# logger_mcu.net
KiCad netlist of a schematic drawn in Altium Designer
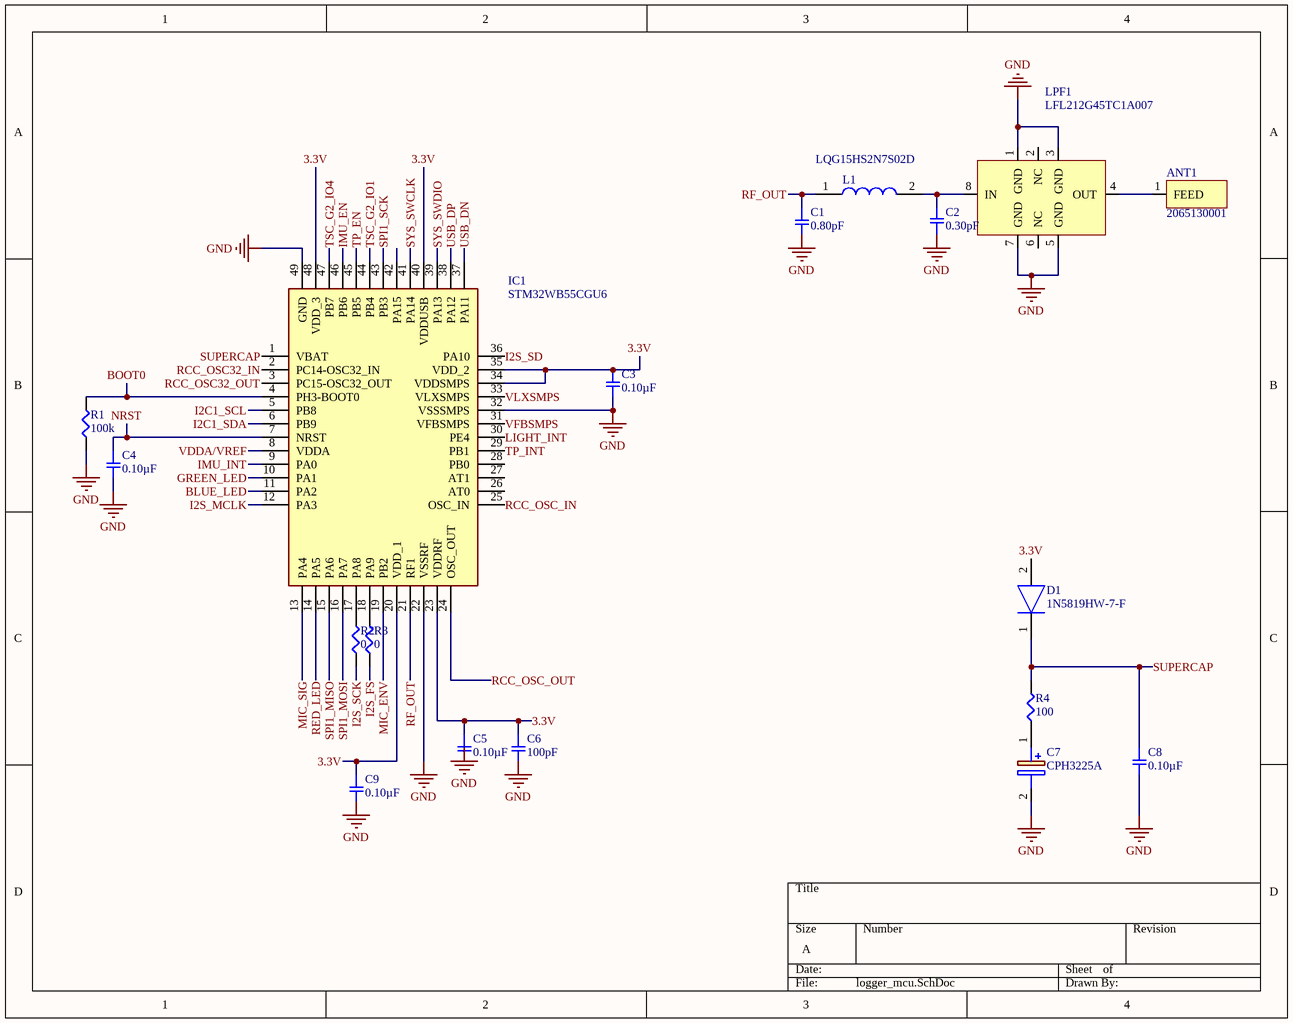
[diagram p0: logger_mcu.SchDoc]

(export (version "E")
  (design (tool "Eeschema 10.0.6"))
  (components
    (comp (ref "ANT1")
      (value "2065130001")
      (footprint "2065130001")
      (libsource (lib "schematic_components") (part "2065130001"))
    )
    (comp (ref "C1")
      (value "0.80pF")
      (footprint "SMD-0402C")
      (description "CAP CER 0.8PF 50V NP0 0402")
      (fields
        (field (name "DIGI-KEY PART NUMBER") "490-6269-1-ND")
        (field (name "PART NUMBER") "GRM1555C1HR80BA01D")
      )
      (libsource (lib "capacitor_murata_0402") (part "GRM1555C1HR80BA01D"))
    )
    (comp (ref "C2")
      (value "0.30pF")
      (footprint "SMD-0402C")
      (description "CAP CER 0.3PF 50V NP0 0402")
      (fields
        (field (name "DIGI-KEY PART NUMBER") "490-6261-1-ND")
        (field (name "PART NUMBER") "GRM1555C1HR30WA01D")
      )
      (libsource (lib "capacitor_murata_0402") (part "GRM1555C1HR30WA01D"))
    )
    (comp (ref "C3")
      (value "0.10µF")
      (footprint "SMD-0402C")
      (description "CAP CER 0.1UF 16V X7R 0402")
      (fields
        (field (name "DIGI-KEY PART NUMBER") "490-4759-1-ND")
        (field (name "PART NUMBER") "GCM155R71C104KA55D")
      )
      (libsource (lib "capacitor_murata_0402") (part "GCM155R71C104KA55D"))
    )
    (comp (ref "C4")
      (value "0.10µF")
      (footprint "SMD-0402C")
      (description "CAP CER 0.1UF 16V X7R 0402")
      (fields
        (field (name "DIGI-KEY PART NUMBER") "490-4759-1-ND")
        (field (name "PART NUMBER") "GCM155R71C104KA55D")
      )
      (libsource (lib "capacitor_murata_0402") (part "GCM155R71C104KA55D"))
    )
    (comp (ref "C5")
      (value "0.10µF")
      (footprint "SMD-0402C")
      (description "CAP CER 0.1UF 16V X7R 0402")
      (fields
        (field (name "DIGI-KEY PART NUMBER") "490-4759-1-ND")
        (field (name "PART NUMBER") "GCM155R71C104KA55D")
      )
      (libsource (lib "capacitor_murata_0402") (part "GCM155R71C104KA55D"))
    )
    (comp (ref "C6")
      (value "100pF")
      (footprint "SMD-0402C")
      (description "CAP CER 100PF 50V NP0 0402")
      (fields
        (field (name "DIGI-KEY PART NUMBER") "490-10669-1-ND")
        (field (name "PART NUMBER") "GCM1555C1H101JA16D")
      )
      (libsource (lib "capacitor_murata_0402") (part "GCM1555C1H101JA16D"))
    )
    (comp (ref "C7")
      (value "CPH3225A")
      (footprint "SamacSys:CPH3225A")
      (description "Capacitor Polarised")
      (fields (field (name "MOUSER PART NUMBER") "628-CPH3225A"))
      (libsource (lib "*") (part "CPH3225A"))
    )
    (comp (ref "C8")
      (value "0.10µF")
      (footprint "SMD-0402C")
      (description "CAP CER 0.1UF 16V X7R 0402")
      (fields
        (field (name "DIGI-KEY PART NUMBER") "490-4759-1-ND")
        (field (name "PART NUMBER") "GCM155R71C104KA55D")
      )
      (libsource (lib "capacitor_murata_0402") (part "GCM155R71C104KA55D"))
    )
    (comp (ref "C9")
      (value "0.10µF")
      (footprint "SMD-0402C")
      (description "CAP CER 0.1UF 16V X7R 0402")
      (fields
        (field (name "DIGI-KEY PART NUMBER") "490-4759-1-ND")
        (field (name "PART NUMBER") "GCM155R71C104KA55D")
      )
      (libsource (lib "capacitor_murata_0402") (part "GCM155R71C104KA55D"))
    )
    (comp (ref "D1")
      (value "1N5819HW-7-F")
      (footprint "SamacSys:SOD3716X145N")
      (description "Diode")
      (fields (field (name "MOUSER PART NUMBER") "621-1N5819HW-F") (field (name "RS PART NUMBER") "7082197P"))
      (libsource (lib "*") (part "1N5819HW-7-F"))
    )
    (comp (ref "IC1")
      (value "STM32WB55CGU6")
      (footprint "SamacSys:QFN50P700X700X65-49N-D")
      (description "Integrated Circuit")
      (fields (field (name "MOUSER PART NUMBER") "511-STM32WB55CGU6"))
      (libsource (lib "SamacSys") (part "STM32WB55CGU6"))
    )
    (comp (ref "L1")
      (value "LQG15HS2N7S02D")
      (footprint "SamacSys:INDC1005X55N")
      (description "Inductor")
      (libsource (lib "SamacSys") (part "LQG15HS2N7S02D"))
    )
    (comp (ref "LPF1")
      (value "LFL212G45TC1A007")
      (footprint "LFL212G45TC1A007")
      (libsource (lib "SamacSys") (part "LFL212G45TC1A007"))
    )
    (comp (ref "R1")
      (value "100k")
      (footprint "SMD-0402-RES")
      (description "RES SMD 100K OHM 1% 1/10W 0402")
      (fields
        (field (name "PART NUMBER") "ERJ-2RKF1003X")
        (field (name "DIGI-KEY PART NUMBER") "P100KLCT-ND")
      )
      (libsource (lib "Panasonic_ERJ_0402") (part "ERJ-2RKF1003X"))
    )
    (comp (ref "R2")
      (value "0")
      (footprint "SMD-0402-RES")
      (description "RES SMD 0K OHM 5% 1/10W 0402")
      (fields (field (name "PART NUMBER") "ERJ-2GEJ103X") (field (name "DIGI-KEY PART NUMBER") "P10KJCT-ND"))
      (libsource (lib "Panasonic_ERJ_0402") (part "ERJ-2GEJ103X"))
    )
    (comp (ref "R3")
      (value "0")
      (footprint "SMD-0402-RES")
      (description "RES SMD 0K OHM 5% 1/10W 0402")
      (fields (field (name "PART NUMBER") "ERJ-2GEJ103X") (field (name "DIGI-KEY PART NUMBER") "P10KJCT-ND"))
      (libsource (lib "Panasonic_ERJ_0402") (part "ERJ-2GEJ103X"))
    )
    (comp (ref "R4")
      (value "100")
      (footprint "SMD-0402-RES")
      (description "RES SMD 100 OHM 5% 1/4W 0603")
      (fields
        (field (name "PART NUMBER") "ERJ-2RKF1003X")
        (field (name "DIGI-KEY PART NUMBER") "P100KLCT-ND")
      )
      (libsource (lib "Panasonic_ERJ_0402") (part "ERJ-2RKF1003X"))
    )
  )
  (nets
    (net (code "1") (name "/3.3V") (class "Default")
      (node (ref "C3") (pin "1") (pinfunction "1_1") (pintype "passive"))
      (node (ref "C5") (pin "1") (pinfunction "1_1") (pintype "passive"))
      (node (ref "C6") (pin "1") (pinfunction "1_1") (pintype "passive"))
      (node (ref "C9") (pin "1") (pinfunction "1_1") (pintype "passive"))
      (node (ref "D1") (pin "2") (pinfunction "A_2") (pintype "passive"))
      (node (ref "IC1") (pin "20") (pinfunction "VDD_1_20") (pintype "passive"))
      (node (ref "IC1") (pin "23") (pinfunction "VDDRF_23") (pintype "passive"))
      (node (ref "IC1") (pin "34") (pinfunction "VDDSMPS_34") (pintype "passive"))
      (node (ref "IC1") (pin "35") (pinfunction "VDD_2_35") (pintype "passive"))
      (node (ref "IC1") (pin "40") (pinfunction "VDDUSB_40") (pintype "passive"))
      (node (ref "IC1") (pin "48") (pinfunction "VDD_3_48") (pintype "passive"))
    )
    (net (code "2") (name "/BLUE_LED") (class "Default")
      (node (ref "IC1") (pin "11") (pinfunction "PA2_11") (pintype "passive"))
    )
    (net (code "3") (name "/BOOT0") (class "Default")
      (node (ref "IC1") (pin "4") (pinfunction "PH3-BOOT0_4") (pintype "passive"))
      (node (ref "R1") (pin "2") (pinfunction "2_2") (pintype "passive"))
    )
    (net (code "4") (name "/GREEN_LED") (class "Default")
      (node (ref "IC1") (pin "10") (pinfunction "PA1_10") (pintype "passive"))
    )
    (net (code "5") (name "/I2C1_SCL") (class "Default")
      (node (ref "IC1") (pin "5") (pinfunction "PB8_5") (pintype "passive"))
    )
    (net (code "6") (name "/I2C1_SDA") (class "Default")
      (node (ref "IC1") (pin "6") (pinfunction "PB9_6") (pintype "passive"))
    )
    (net (code "7") (name "/I2S_FS") (class "Default")
      (node (ref "R3") (pin "1") (pinfunction "1_1") (pintype "passive"))
    )
    (net (code "8") (name "/I2S_MCLK") (class "Default")
      (node (ref "IC1") (pin "12") (pinfunction "PA3_12") (pintype "passive"))
    )
    (net (code "9") (name "/I2S_SCK") (class "Default")
      (node (ref "R2") (pin "1") (pinfunction "1_1") (pintype "passive"))
    )
    (net (code "10") (name "/I2S_SD") (class "Default")
      (node (ref "IC1") (pin "36") (pinfunction "PA10_36") (pintype "passive"))
    )
    (net (code "11") (name "/IMU_EN") (class "Default")
      (node (ref "IC1") (pin "46") (pinfunction "PB6_46") (pintype "passive"))
    )
    (net (code "12") (name "/IMU_INT") (class "Default")
      (node (ref "IC1") (pin "9") (pinfunction "PA0_9") (pintype "passive"))
    )
    (net (code "13") (name "/LIGHT_INT") (class "Default")
      (node (ref "IC1") (pin "30") (pinfunction "PE4_30") (pintype "passive"))
    )
    (net (code "14") (name "/MIC_ENV") (class "Default")
      (node (ref "IC1") (pin "19") (pinfunction "PB2_19") (pintype "passive"))
    )
    (net (code "15") (name "/MIC_SIG") (class "Default")
      (node (ref "IC1") (pin "13") (pinfunction "PA4_13") (pintype "passive"))
    )
    (net (code "16") (name "/NRST") (class "Default")
      (node (ref "C4") (pin "1") (pinfunction "1_1") (pintype "passive"))
      (node (ref "IC1") (pin "7") (pinfunction "NRST_7") (pintype "passive"))
    )
    (net (code "17") (name "/RCC_OSC32_IN") (class "Default")
      (node (ref "IC1") (pin "2") (pinfunction "PC14-OSC32_IN_2") (pintype "passive"))
    )
    (net (code "18") (name "/RCC_OSC32_OUT") (class "Default")
      (node (ref "IC1") (pin "3") (pinfunction "PC15-OSC32_OUT_3") (pintype "passive"))
    )
    (net (code "19") (name "/RCC_OSC_IN") (class "Default")
      (node (ref "IC1") (pin "25") (pinfunction "OSC_IN_25") (pintype "passive"))
    )
    (net (code "20") (name "/RCC_OSC_OUT") (class "Default")
      (node (ref "IC1") (pin "24") (pinfunction "OSC_OUT_24") (pintype "passive"))
    )
    (net (code "21") (name "/RED_LED") (class "Default")
      (node (ref "IC1") (pin "14") (pinfunction "PA5_14") (pintype "passive"))
    )
    (net (code "22") (name "/RF_OUT") (class "Default")
      (node (ref "C1") (pin "1") (pinfunction "1_1") (pintype "passive"))
      (node (ref "IC1") (pin "21") (pinfunction "RF1_21") (pintype "passive"))
      (node (ref "L1") (pin "1") (pinfunction "1_1") (pintype "passive"))
    )
    (net (code "23") (name "/SPI1_MISO") (class "Default")
      (node (ref "IC1") (pin "15") (pinfunction "PA6_15") (pintype "passive"))
    )
    (net (code "24") (name "/SPI1_MOSI") (class "Default")
      (node (ref "IC1") (pin "16") (pinfunction "PA7_16") (pintype "passive"))
    )
    (net (code "25") (name "/SPI1_SCK") (class "Default")
      (node (ref "IC1") (pin "43") (pinfunction "PB3_43") (pintype "passive"))
    )
    (net (code "26") (name "/SUPERCAP") (class "Default")
      (node (ref "C8") (pin "1") (pinfunction "1_1") (pintype "passive"))
      (node (ref "D1") (pin "1") (pinfunction "K_1") (pintype "passive"))
      (node (ref "IC1") (pin "1") (pinfunction "VBAT_1") (pintype "passive"))
      (node (ref "R4") (pin "2") (pinfunction "2_2") (pintype "passive"))
    )
    (net (code "27") (name "/SYS_SWCLK") (class "Default")
      (node (ref "IC1") (pin "41") (pinfunction "PA14_41") (pintype "passive"))
    )
    (net (code "28") (name "/SYS_SWDIO") (class "Default")
      (node (ref "IC1") (pin "39") (pinfunction "PA13_39") (pintype "passive"))
    )
    (net (code "29") (name "/TP_EN") (class "Default")
      (node (ref "IC1") (pin "45") (pinfunction "PB5_45") (pintype "passive"))
    )
    (net (code "30") (name "/TP_INT") (class "Default")
      (node (ref "IC1") (pin "29") (pinfunction "PB1_29") (pintype "passive"))
    )
    (net (code "31") (name "/TSC_G2_IO1") (class "Default")
      (node (ref "IC1") (pin "44") (pinfunction "PB4_44") (pintype "passive"))
    )
    (net (code "32") (name "/TSC_G2_IO4") (class "Default")
      (node (ref "IC1") (pin "47") (pinfunction "PB7_47") (pintype "passive"))
    )
    (net (code "33") (name "/USB_DN") (class "Default")
      (node (ref "IC1") (pin "37") (pinfunction "PA11_37") (pintype "passive"))
    )
    (net (code "34") (name "/USB_DP") (class "Default")
      (node (ref "IC1") (pin "38") (pinfunction "PA12_38") (pintype "passive"))
    )
    (net (code "35") (name "/VDDA{slash}VREF") (class "Default")
      (node (ref "IC1") (pin "8") (pinfunction "VDDA_8") (pintype "passive"))
    )
    (net (code "36") (name "/VFBSMPS") (class "Default")
      (node (ref "IC1") (pin "31") (pinfunction "VFBSMPS_31") (pintype "passive"))
    )
    (net (code "37") (name "/VLXSMPS") (class "Default")
      (node (ref "IC1") (pin "33") (pinfunction "VLXSMPS_33") (pintype "passive"))
    )
    (net (code "38") (name "GND") (class "Default")
      (node (ref "C1") (pin "2") (pinfunction "2_2") (pintype "passive"))
      (node (ref "C2") (pin "1") (pinfunction "1_1") (pintype "passive"))
      (node (ref "C3") (pin "2") (pinfunction "2_2") (pintype "passive"))
      (node (ref "C4") (pin "2") (pinfunction "2_2") (pintype "passive"))
      (node (ref "C6") (pin "2") (pinfunction "2_2") (pintype "passive"))
      (node (ref "C7") (pin "2") (pinfunction "-_2") (pintype "passive"))
      (node (ref "C8") (pin "2") (pinfunction "2_2") (pintype "passive"))
      (node (ref "C9") (pin "2") (pinfunction "2_2") (pintype "passive"))
      (node (ref "IC1") (pin "22") (pinfunction "VSSRF_22") (pintype "passive"))
      (node (ref "IC1") (pin "32") (pinfunction "VSSSMPS_32") (pintype "passive"))
      (node (ref "IC1") (pin "49") (pinfunction "GND_49") (pintype "passive"))
      (node (ref "LPF1") (pin "1") (pinfunction "GND_1") (pintype "passive"))
      (node (ref "LPF1") (pin "3") (pinfunction "GND_3") (pintype "passive"))
      (node (ref "LPF1") (pin "5") (pinfunction "GND_5") (pintype "passive"))
      (node (ref "LPF1") (pin "7") (pinfunction "GND_7") (pintype "passive"))
      (node (ref "R1") (pin "1") (pinfunction "1_1") (pintype "passive"))
    )
    (net (code "39") (name "Net-(ANT1-FEED)") (class "Default")
      (node (ref "ANT1") (pin "1") (pinfunction "FEED_1") (pintype "passive"))
      (node (ref "LPF1") (pin "4") (pinfunction "OUT_4") (pintype "passive"))
    )
    (net (code "40") (name "Net-(C7-+)") (class "Default")
      (node (ref "C7") (pin "1") (pinfunction "+_1") (pintype "passive"))
      (node (ref "R4") (pin "1") (pinfunction "1_1") (pintype "passive"))
    )
    (net (code "41") (name "Net-(IC1-PA8)") (class "Default")
      (node (ref "IC1") (pin "17") (pinfunction "PA8_17") (pintype "passive"))
      (node (ref "R2") (pin "2") (pinfunction "2_2") (pintype "passive"))
    )
    (net (code "42") (name "Net-(IC1-PA9)") (class "Default")
      (node (ref "IC1") (pin "18") (pinfunction "PA9_18") (pintype "passive"))
      (node (ref "R3") (pin "2") (pinfunction "2_2") (pintype "passive"))
    )
    (net (code "43") (name "Net-(LPF1-IN)") (class "Default")
      (node (ref "C2") (pin "2") (pinfunction "2_2") (pintype "passive"))
      (node (ref "L1") (pin "2") (pinfunction "2_2") (pintype "passive"))
      (node (ref "LPF1") (pin "8") (pinfunction "IN_8") (pintype "passive"))
    )
    (net (code "44") (name "unconnected-(C5-Pad2)") (class "Default")
      (node (ref "C5") (pin "2") (pinfunction "2_2") (pintype "passive"))
    )
    (net (code "45") (name "unconnected-(IC1-AT0-Pad26)") (class "Default")
      (node (ref "IC1") (pin "26") (pinfunction "AT0_26") (pintype "passive"))
    )
    (net (code "46") (name "unconnected-(IC1-AT1-Pad27)") (class "Default")
      (node (ref "IC1") (pin "27") (pinfunction "AT1_27") (pintype "passive"))
    )
    (net (code "47") (name "unconnected-(IC1-PA15-Pad42)") (class "Default")
      (node (ref "IC1") (pin "42") (pinfunction "PA15_42") (pintype "passive"))
    )
    (net (code "48") (name "unconnected-(IC1-PB0-Pad28)") (class "Default")
      (node (ref "IC1") (pin "28") (pinfunction "PB0_28") (pintype "passive"))
    )
    (net (code "49") (name "unconnected-(LPF1-NC-Pad2)") (class "Default")
      (node (ref "LPF1") (pin "2") (pinfunction "NC_2") (pintype "passive"))
    )
    (net (code "50") (name "unconnected-(LPF1-NC-Pad6)") (class "Default")
      (node (ref "LPF1") (pin "6") (pinfunction "NC_6") (pintype "passive"))
    )
  )
)
